# shield.net
KiCad netlist of a schematic drawn in Altium Designer
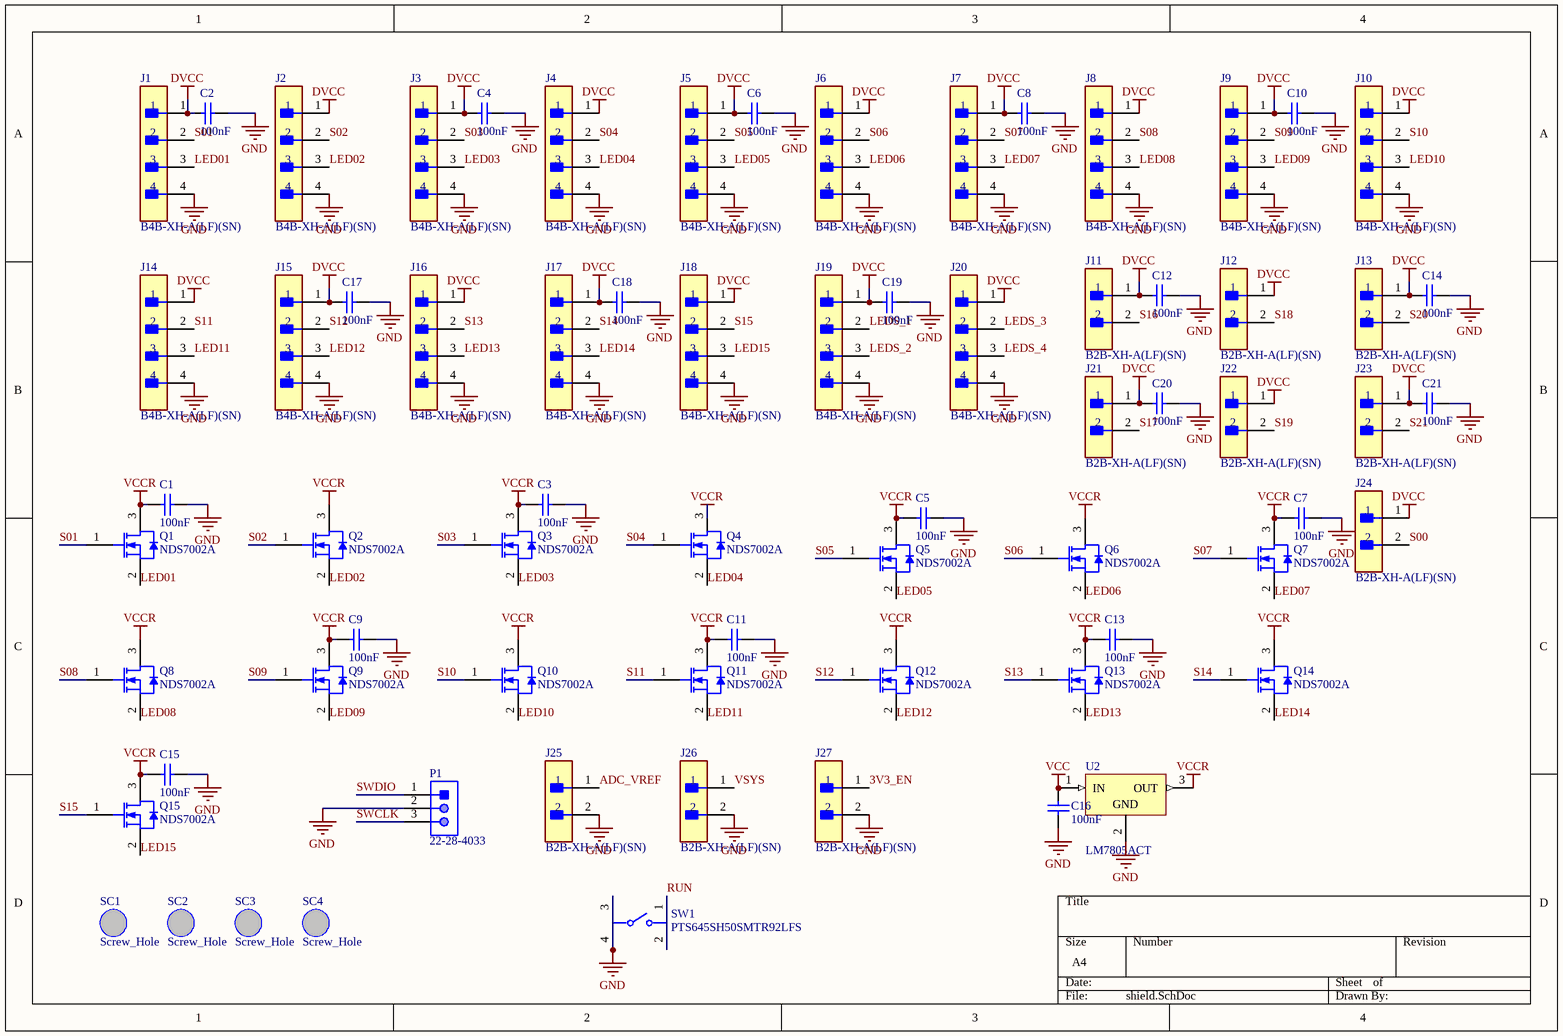
[diagram p0: shield.SchDoc]

(export (version "E")
  (design (tool "Eeschema 10.0.6"))
  (components
    (comp (ref "C1")
      (value "100nF")
      (footprint "0805C")
      (description "Capacitor")
      (fields (field (name "REVIEWED BY") "RM - 2018/08/05"))
      (libsource (lib "DSO") (part "C"))
    )
    (comp (ref "C2")
      (value "100nF")
      (footprint "0805C")
      (description "Capacitor")
      (fields (field (name "REVIEWED BY") "RM - 2018/08/05"))
      (libsource (lib "DSO") (part "C"))
    )
    (comp (ref "C3")
      (value "100nF")
      (footprint "0805C")
      (description "Capacitor")
      (fields (field (name "REVIEWED BY") "RM - 2018/08/05"))
      (libsource (lib "DSO") (part "C"))
    )
    (comp (ref "C4")
      (value "100nF")
      (footprint "0805C")
      (description "Capacitor")
      (fields (field (name "REVIEWED BY") "RM - 2018/08/05"))
      (libsource (lib "DSO") (part "C"))
    )
    (comp (ref "C5")
      (value "100nF")
      (footprint "0805C")
      (description "Capacitor")
      (fields (field (name "REVIEWED BY") "RM - 2018/08/05"))
      (libsource (lib "DSO") (part "C"))
    )
    (comp (ref "C6")
      (value "100nF")
      (footprint "0805C")
      (description "Capacitor")
      (fields (field (name "REVIEWED BY") "RM - 2018/08/05"))
      (libsource (lib "DSO") (part "C"))
    )
    (comp (ref "C7")
      (value "100nF")
      (footprint "0805C")
      (description "Capacitor")
      (fields (field (name "REVIEWED BY") "RM - 2018/08/05"))
      (libsource (lib "DSO") (part "C"))
    )
    (comp (ref "C8")
      (value "100nF")
      (footprint "0805C")
      (description "Capacitor")
      (fields (field (name "REVIEWED BY") "RM - 2018/08/05"))
      (libsource (lib "DSO") (part "C"))
    )
    (comp (ref "C9")
      (value "100nF")
      (footprint "0805C")
      (description "Capacitor")
      (fields (field (name "REVIEWED BY") "RM - 2018/08/05"))
      (libsource (lib "DSO") (part "C"))
    )
    (comp (ref "C10")
      (value "100nF")
      (footprint "0805C")
      (description "Capacitor")
      (fields (field (name "REVIEWED BY") "RM - 2018/08/05"))
      (libsource (lib "DSO") (part "C"))
    )
    (comp (ref "C11")
      (value "100nF")
      (footprint "0805C")
      (description "Capacitor")
      (fields (field (name "REVIEWED BY") "RM - 2018/08/05"))
      (libsource (lib "DSO") (part "C"))
    )
    (comp (ref "C12")
      (value "100nF")
      (footprint "0805C")
      (description "Capacitor")
      (fields (field (name "REVIEWED BY") "RM - 2018/08/05"))
      (libsource (lib "DSO") (part "C"))
    )
    (comp (ref "C13")
      (value "100nF")
      (footprint "0805C")
      (description "Capacitor")
      (fields (field (name "REVIEWED BY") "RM - 2018/08/05"))
      (libsource (lib "DSO") (part "C"))
    )
    (comp (ref "C14")
      (value "100nF")
      (footprint "0805C")
      (description "Capacitor")
      (fields (field (name "REVIEWED BY") "RM - 2018/08/05"))
      (libsource (lib "DSO") (part "C"))
    )
    (comp (ref "C15")
      (value "100nF")
      (footprint "0805C")
      (description "Capacitor")
      (fields (field (name "REVIEWED BY") "RM - 2018/08/05"))
      (libsource (lib "DSO") (part "C"))
    )
    (comp (ref "C16")
      (value "100nF")
      (footprint "0805C")
      (description "Capacitor")
      (fields (field (name "REVIEWED BY") "RM - 2018/08/05"))
      (libsource (lib "DSO") (part "C"))
    )
    (comp (ref "C17")
      (value "100nF")
      (footprint "0805C")
      (description "Capacitor")
      (fields (field (name "REVIEWED BY") "RM - 2018/08/05"))
      (libsource (lib "DSO") (part "C"))
    )
    (comp (ref "C18")
      (value "100nF")
      (footprint "0805C")
      (description "Capacitor")
      (fields (field (name "REVIEWED BY") "RM - 2018/08/05"))
      (libsource (lib "DSO") (part "C"))
    )
    (comp (ref "C19")
      (value "100nF")
      (footprint "0805C")
      (description "Capacitor")
      (fields (field (name "REVIEWED BY") "RM - 2018/08/05"))
      (libsource (lib "DSO") (part "C"))
    )
    (comp (ref "C20")
      (value "100nF")
      (footprint "0805C")
      (description "Capacitor")
      (fields (field (name "REVIEWED BY") "RM - 2018/08/05"))
      (libsource (lib "DSO") (part "C"))
    )
    (comp (ref "C21")
      (value "100nF")
      (footprint "0805C")
      (description "Capacitor")
      (fields (field (name "REVIEWED BY") "RM - 2018/08/05"))
      (libsource (lib "DSO") (part "C"))
    )
    (comp (ref "J1")
      (value "B4B-XH-A(LF)(SN)")
      (footprint "FP-B4B-XH-A_LF_SN-MFG")
      (description "CONN HEADER VERT 4POS 2.5MM")
      (libsource (lib "Altium Content Vault") (part "299a8cea1bdcbc3624fe62c390fa72c"))
    )
    (comp (ref "J2")
      (value "B4B-XH-A(LF)(SN)")
      (footprint "FP-B4B-XH-A_LF_SN-MFG")
      (description "CONN HEADER VERT 4POS 2.5MM")
      (libsource (lib "Altium Content Vault") (part "299a8cea1bdcbc3624fe62c390fa72c"))
    )
    (comp (ref "J3")
      (value "B4B-XH-A(LF)(SN)")
      (footprint "FP-B4B-XH-A_LF_SN-MFG")
      (description "CONN HEADER VERT 4POS 2.5MM")
      (libsource (lib "Altium Content Vault") (part "299a8cea1bdcbc3624fe62c390fa72c"))
    )
    (comp (ref "J4")
      (value "B4B-XH-A(LF)(SN)")
      (footprint "FP-B4B-XH-A_LF_SN-MFG")
      (description "CONN HEADER VERT 4POS 2.5MM")
      (libsource (lib "Altium Content Vault") (part "299a8cea1bdcbc3624fe62c390fa72c"))
    )
    (comp (ref "J5")
      (value "B4B-XH-A(LF)(SN)")
      (footprint "FP-B4B-XH-A_LF_SN-MFG")
      (description "CONN HEADER VERT 4POS 2.5MM")
      (libsource (lib "Altium Content Vault") (part "299a8cea1bdcbc3624fe62c390fa72c"))
    )
    (comp (ref "J6")
      (value "B4B-XH-A(LF)(SN)")
      (footprint "FP-B4B-XH-A_LF_SN-MFG")
      (description "CONN HEADER VERT 4POS 2.5MM")
      (libsource (lib "Altium Content Vault") (part "299a8cea1bdcbc3624fe62c390fa72c"))
    )
    (comp (ref "J7")
      (value "B4B-XH-A(LF)(SN)")
      (footprint "FP-B4B-XH-A_LF_SN-MFG")
      (description "CONN HEADER VERT 4POS 2.5MM")
      (libsource (lib "Altium Content Vault") (part "299a8cea1bdcbc3624fe62c390fa72c"))
    )
    (comp (ref "J8")
      (value "B4B-XH-A(LF)(SN)")
      (footprint "FP-B4B-XH-A_LF_SN-MFG")
      (description "CONN HEADER VERT 4POS 2.5MM")
      (libsource (lib "Altium Content Vault") (part "299a8cea1bdcbc3624fe62c390fa72c"))
    )
    (comp (ref "J9")
      (value "B4B-XH-A(LF)(SN)")
      (footprint "FP-B4B-XH-A_LF_SN-MFG")
      (description "CONN HEADER VERT 4POS 2.5MM")
      (libsource (lib "Altium Content Vault") (part "299a8cea1bdcbc3624fe62c390fa72c"))
    )
    (comp (ref "J10")
      (value "B4B-XH-A(LF)(SN)")
      (footprint "FP-B4B-XH-A_LF_SN-MFG")
      (description "CONN HEADER VERT 4POS 2.5MM")
      (libsource (lib "Altium Content Vault") (part "299a8cea1bdcbc3624fe62c390fa72c"))
    )
    (comp (ref "J11")
      (value "B2B-XH-A(LF)(SN)")
      (footprint "FP-B2B-XH-A_LF_SN-MFG")
      (description "CONN HEADER VERT 2POS 2.5MM")
      (libsource (lib "Altium Content Vault") (part "3bc925449376181038e59eaffc5286c"))
    )
    (comp (ref "J12")
      (value "B2B-XH-A(LF)(SN)")
      (footprint "FP-B2B-XH-A_LF_SN-MFG")
      (description "CONN HEADER VERT 2POS 2.5MM")
      (libsource (lib "Altium Content Vault") (part "3bc925449376181038e59eaffc5286c"))
    )
    (comp (ref "J13")
      (value "B2B-XH-A(LF)(SN)")
      (footprint "FP-B2B-XH-A_LF_SN-MFG")
      (description "CONN HEADER VERT 2POS 2.5MM")
      (libsource (lib "Altium Content Vault") (part "3bc925449376181038e59eaffc5286c"))
    )
    (comp (ref "J14")
      (value "B4B-XH-A(LF)(SN)")
      (footprint "FP-B4B-XH-A_LF_SN-MFG")
      (description "CONN HEADER VERT 4POS 2.5MM")
      (libsource (lib "Altium Content Vault") (part "299a8cea1bdcbc3624fe62c390fa72c"))
    )
    (comp (ref "J15")
      (value "B4B-XH-A(LF)(SN)")
      (footprint "FP-B4B-XH-A_LF_SN-MFG")
      (description "CONN HEADER VERT 4POS 2.5MM")
      (libsource (lib "Altium Content Vault") (part "299a8cea1bdcbc3624fe62c390fa72c"))
    )
    (comp (ref "J16")
      (value "B4B-XH-A(LF)(SN)")
      (footprint "FP-B4B-XH-A_LF_SN-MFG")
      (description "CONN HEADER VERT 4POS 2.5MM")
      (libsource (lib "Altium Content Vault") (part "299a8cea1bdcbc3624fe62c390fa72c"))
    )
    (comp (ref "J17")
      (value "B4B-XH-A(LF)(SN)")
      (footprint "FP-B4B-XH-A_LF_SN-MFG")
      (description "CONN HEADER VERT 4POS 2.5MM")
      (libsource (lib "Altium Content Vault") (part "299a8cea1bdcbc3624fe62c390fa72c"))
    )
    (comp (ref "J18")
      (value "B4B-XH-A(LF)(SN)")
      (footprint "FP-B4B-XH-A_LF_SN-MFG")
      (description "CONN HEADER VERT 4POS 2.5MM")
      (libsource (lib "Altium Content Vault") (part "299a8cea1bdcbc3624fe62c390fa72c"))
    )
    (comp (ref "J19")
      (value "B4B-XH-A(LF)(SN)")
      (footprint "FP-B4B-XH-A_LF_SN-MFG")
      (description "CONN HEADER VERT 4POS 2.5MM")
      (libsource (lib "Altium Content Vault") (part "299a8cea1bdcbc3624fe62c390fa72c"))
    )
    (comp (ref "J20")
      (value "B4B-XH-A(LF)(SN)")
      (footprint "FP-B4B-XH-A_LF_SN-MFG")
      (description "CONN HEADER VERT 4POS 2.5MM")
      (libsource (lib "Altium Content Vault") (part "299a8cea1bdcbc3624fe62c390fa72c"))
    )
    (comp (ref "J21")
      (value "B2B-XH-A(LF)(SN)")
      (footprint "FP-B2B-XH-A_LF_SN-MFG")
      (description "CONN HEADER VERT 2POS 2.5MM")
      (libsource (lib "Altium Content Vault") (part "3bc925449376181038e59eaffc5286c"))
    )
    (comp (ref "J22")
      (value "B2B-XH-A(LF)(SN)")
      (footprint "FP-B2B-XH-A_LF_SN-MFG")
      (description "CONN HEADER VERT 2POS 2.5MM")
      (libsource (lib "Altium Content Vault") (part "3bc925449376181038e59eaffc5286c"))
    )
    (comp (ref "J23")
      (value "B2B-XH-A(LF)(SN)")
      (footprint "FP-B2B-XH-A_LF_SN-MFG")
      (description "CONN HEADER VERT 2POS 2.5MM")
      (libsource (lib "Altium Content Vault") (part "3bc925449376181038e59eaffc5286c"))
    )
    (comp (ref "J24")
      (value "B2B-XH-A(LF)(SN)")
      (footprint "FP-B2B-XH-A_LF_SN-MFG")
      (description "CONN HEADER VERT 2POS 2.5MM")
      (libsource (lib "Altium Content Vault") (part "3bc925449376181038e59eaffc5286c"))
    )
    (comp (ref "J25")
      (value "B2B-XH-A(LF)(SN)")
      (footprint "FP-B2B-XH-A_LF_SN-MFG")
      (description "CONN HEADER VERT 2POS 2.5MM")
      (libsource (lib "Altium Content Vault") (part "3bc925449376181038e59eaffc5286c"))
    )
    (comp (ref "J26")
      (value "B2B-XH-A(LF)(SN)")
      (footprint "FP-B2B-XH-A_LF_SN-MFG")
      (description "CONN HEADER VERT 2POS 2.5MM")
      (libsource (lib "Altium Content Vault") (part "3bc925449376181038e59eaffc5286c"))
    )
    (comp (ref "J27")
      (value "B2B-XH-A(LF)(SN)")
      (footprint "FP-B2B-XH-A_LF_SN-MFG")
      (description "CONN HEADER VERT 2POS 2.5MM")
      (libsource (lib "Altium Content Vault") (part "3bc925449376181038e59eaffc5286c"))
    )
    (comp (ref "P1")
      (value "22-28-4033")
      (footprint "MOLX-22-28-4033_V")
      (description "Male Header, Pitch 2.54 mm, 1 x 3 Position, Height 8.38 mm, Tail Length 3.18 mm, RoHS, Bulk")
      (fields (field (name "MANUFACTURER") "Molex"))
      (libsource (lib "Altium Content Vault") (part "CN-1P-M-R3"))
    )
    (comp (ref "Q1")
      (value "NDS7002A")
      (footprint "FAIR-SOT23-3_V")
      (fields (field (name "MANUFACTURER") "Fairchild Semiconductor"))
      (libsource (lib "Altium Content Vault") (part "NEMOS-GSD-3"))
    )
    (comp (ref "Q2")
      (value "NDS7002A")
      (footprint "FAIR-SOT23-3_V")
      (fields (field (name "MANUFACTURER") "Fairchild Semiconductor"))
      (libsource (lib "Altium Content Vault") (part "NEMOS-GSD-3"))
    )
    (comp (ref "Q3")
      (value "NDS7002A")
      (footprint "FAIR-SOT23-3_V")
      (fields (field (name "MANUFACTURER") "Fairchild Semiconductor"))
      (libsource (lib "Altium Content Vault") (part "NEMOS-GSD-3"))
    )
    (comp (ref "Q4")
      (value "NDS7002A")
      (footprint "FAIR-SOT23-3_V")
      (fields (field (name "MANUFACTURER") "Fairchild Semiconductor"))
      (libsource (lib "Altium Content Vault") (part "NEMOS-GSD-3"))
    )
    (comp (ref "Q5")
      (value "NDS7002A")
      (footprint "FAIR-SOT23-3_V")
      (fields (field (name "MANUFACTURER") "Fairchild Semiconductor"))
      (libsource (lib "Altium Content Vault") (part "NEMOS-GSD-3"))
    )
    (comp (ref "Q6")
      (value "NDS7002A")
      (footprint "FAIR-SOT23-3_V")
      (fields (field (name "MANUFACTURER") "Fairchild Semiconductor"))
      (libsource (lib "Altium Content Vault") (part "NEMOS-GSD-3"))
    )
    (comp (ref "Q7")
      (value "NDS7002A")
      (footprint "FAIR-SOT23-3_V")
      (fields (field (name "MANUFACTURER") "Fairchild Semiconductor"))
      (libsource (lib "Altium Content Vault") (part "NEMOS-GSD-3"))
    )
    (comp (ref "Q8")
      (value "NDS7002A")
      (footprint "FAIR-SOT23-3_V")
      (fields (field (name "MANUFACTURER") "Fairchild Semiconductor"))
      (libsource (lib "Altium Content Vault") (part "NEMOS-GSD-3"))
    )
    (comp (ref "Q9")
      (value "NDS7002A")
      (footprint "FAIR-SOT23-3_V")
      (fields (field (name "MANUFACTURER") "Fairchild Semiconductor"))
      (libsource (lib "Altium Content Vault") (part "NEMOS-GSD-3"))
    )
    (comp (ref "Q10")
      (value "NDS7002A")
      (footprint "FAIR-SOT23-3_V")
      (fields (field (name "MANUFACTURER") "Fairchild Semiconductor"))
      (libsource (lib "Altium Content Vault") (part "NEMOS-GSD-3"))
    )
    (comp (ref "Q11")
      (value "NDS7002A")
      (footprint "FAIR-SOT23-3_V")
      (fields (field (name "MANUFACTURER") "Fairchild Semiconductor"))
      (libsource (lib "Altium Content Vault") (part "NEMOS-GSD-3"))
    )
    (comp (ref "Q12")
      (value "NDS7002A")
      (footprint "FAIR-SOT23-3_V")
      (fields (field (name "MANUFACTURER") "Fairchild Semiconductor"))
      (libsource (lib "Altium Content Vault") (part "NEMOS-GSD-3"))
    )
    (comp (ref "Q13")
      (value "NDS7002A")
      (footprint "FAIR-SOT23-3_V")
      (fields (field (name "MANUFACTURER") "Fairchild Semiconductor"))
      (libsource (lib "Altium Content Vault") (part "NEMOS-GSD-3"))
    )
    (comp (ref "Q14")
      (value "NDS7002A")
      (footprint "FAIR-SOT23-3_V")
      (fields (field (name "MANUFACTURER") "Fairchild Semiconductor"))
      (libsource (lib "Altium Content Vault") (part "NEMOS-GSD-3"))
    )
    (comp (ref "Q15")
      (value "NDS7002A")
      (footprint "FAIR-SOT23-3_V")
      (fields (field (name "MANUFACTURER") "Fairchild Semiconductor"))
      (libsource (lib "Altium Content Vault") (part "NEMOS-GSD-3"))
    )
    (comp (ref "SC1")
      (value "Screw_Hole")
      (footprint "Screw_Hole")
      (description "Screw Hole")
      (libsource (lib "DSO") (part "Screw_Hole"))
    )
    (comp (ref "SC2")
      (value "Screw_Hole")
      (footprint "Screw_Hole")
      (description "Screw Hole")
      (libsource (lib "DSO") (part "Screw_Hole"))
    )
    (comp (ref "SC3")
      (value "Screw_Hole")
      (footprint "Screw_Hole")
      (description "Screw Hole")
      (libsource (lib "DSO") (part "Screw_Hole"))
    )
    (comp (ref "SC4")
      (value "Screw_Hole")
      (footprint "Screw_Hole")
      (description "Screw Hole")
      (libsource (lib "DSO") (part "Screw_Hole"))
    )
    (comp (ref "SW1")
      (value "PTS645SH50SMTR92LFS")
      (footprint "FP-PTS645SH50SMTR92LFS-MFG")
      (description "SWITCH TACTILE SPST-NO 0.05A 12V")
      (libsource (lib "Altium Content Vault") (part "1adf0dd01260c80cf25a44bfd6b99ba"))
    )
    (comp (ref "U2")
      (value "LM7805ACT")
      (footprint "FAIR-TO-220-3")
      (description "Positive Voltage Regulator, 5 V, 1 A, 0 to 125 degC, 3-Pin TO-220, RoHS, Tube")
      (fields (field (name "MANUFACTURER") "Fairchild"))
      (libsource (lib "Altium Content Vault") (part "FAIR-LM7805CT-TO220-3"))
    )
  )
  (nets
    (net (code "1") (name "/3V3_EN") (class "Default")
      (node (ref "J27") (pin "1") (pinfunction "1_1") (pintype "passive"))
    )
    (net (code "2") (name "/ADC_VREF") (class "Default")
      (node (ref "J25") (pin "1") (pinfunction "1_1") (pintype "passive"))
    )
    (net (code "3") (name "/LED01") (class "Default")
      (node (ref "J1") (pin "3") (pinfunction "3_3") (pintype "passive"))
      (node (ref "Q1") (pin "2") (pinfunction "S_2") (pintype "passive"))
    )
    (net (code "4") (name "/LED02") (class "Default")
      (node (ref "J2") (pin "3") (pinfunction "3_3") (pintype "passive"))
      (node (ref "Q2") (pin "2") (pinfunction "S_2") (pintype "passive"))
    )
    (net (code "5") (name "/LED03") (class "Default")
      (node (ref "J3") (pin "3") (pinfunction "3_3") (pintype "passive"))
      (node (ref "Q3") (pin "2") (pinfunction "S_2") (pintype "passive"))
    )
    (net (code "6") (name "/LED04") (class "Default")
      (node (ref "J4") (pin "3") (pinfunction "3_3") (pintype "passive"))
      (node (ref "Q4") (pin "2") (pinfunction "S_2") (pintype "passive"))
    )
    (net (code "7") (name "/LED05") (class "Default")
      (node (ref "J5") (pin "3") (pinfunction "3_3") (pintype "passive"))
      (node (ref "Q5") (pin "2") (pinfunction "S_2") (pintype "passive"))
    )
    (net (code "8") (name "/LED06") (class "Default")
      (node (ref "J6") (pin "3") (pinfunction "3_3") (pintype "passive"))
      (node (ref "Q6") (pin "2") (pinfunction "S_2") (pintype "passive"))
    )
    (net (code "9") (name "/LED07") (class "Default")
      (node (ref "J7") (pin "3") (pinfunction "3_3") (pintype "passive"))
      (node (ref "Q7") (pin "2") (pinfunction "S_2") (pintype "passive"))
    )
    (net (code "10") (name "/LED08") (class "Default")
      (node (ref "J8") (pin "3") (pinfunction "3_3") (pintype "passive"))
      (node (ref "Q8") (pin "2") (pinfunction "S_2") (pintype "passive"))
    )
    (net (code "11") (name "/LED09") (class "Default")
      (node (ref "J9") (pin "3") (pinfunction "3_3") (pintype "passive"))
      (node (ref "Q9") (pin "2") (pinfunction "S_2") (pintype "passive"))
    )
    (net (code "12") (name "/LED10") (class "Default")
      (node (ref "J10") (pin "3") (pinfunction "3_3") (pintype "passive"))
      (node (ref "Q10") (pin "2") (pinfunction "S_2") (pintype "passive"))
    )
    (net (code "13") (name "/LED11") (class "Default")
      (node (ref "J14") (pin "3") (pinfunction "3_3") (pintype "passive"))
      (node (ref "Q11") (pin "2") (pinfunction "S_2") (pintype "passive"))
    )
    (net (code "14") (name "/LED12") (class "Default")
      (node (ref "J15") (pin "3") (pinfunction "3_3") (pintype "passive"))
      (node (ref "Q12") (pin "2") (pinfunction "S_2") (pintype "passive"))
    )
    (net (code "15") (name "/LED13") (class "Default")
      (node (ref "J16") (pin "3") (pinfunction "3_3") (pintype "passive"))
      (node (ref "Q13") (pin "2") (pinfunction "S_2") (pintype "passive"))
    )
    (net (code "16") (name "/LED14") (class "Default")
      (node (ref "J17") (pin "3") (pinfunction "3_3") (pintype "passive"))
      (node (ref "Q14") (pin "2") (pinfunction "S_2") (pintype "passive"))
    )
    (net (code "17") (name "/LED15") (class "Default")
      (node (ref "J18") (pin "3") (pinfunction "3_3") (pintype "passive"))
      (node (ref "Q15") (pin "2") (pinfunction "S_2") (pintype "passive"))
    )
    (net (code "18") (name "/LEDS_1") (class "Default")
      (node (ref "J19") (pin "2") (pinfunction "2_2") (pintype "passive"))
    )
    (net (code "19") (name "/LEDS_2") (class "Default")
      (node (ref "J19") (pin "3") (pinfunction "3_3") (pintype "passive"))
    )
    (net (code "20") (name "/LEDS_3") (class "Default")
      (node (ref "J20") (pin "2") (pinfunction "2_2") (pintype "passive"))
    )
    (net (code "21") (name "/LEDS_4") (class "Default")
      (node (ref "J20") (pin "3") (pinfunction "3_3") (pintype "passive"))
    )
    (net (code "22") (name "/RUN") (class "Default")
      (node (ref "SW1") (pin "1") (pinfunction "1_1") (pintype "passive"))
      (node (ref "SW1") (pin "2") (pinfunction "2_2") (pintype "passive"))
    )
    (net (code "23") (name "/S00") (class "Default")
      (node (ref "J24") (pin "2") (pinfunction "2_2") (pintype "passive"))
    )
    (net (code "24") (name "/S01") (class "Default")
      (node (ref "J1") (pin "2") (pinfunction "2_2") (pintype "passive"))
      (node (ref "Q1") (pin "1") (pinfunction "G_1") (pintype "passive"))
    )
    (net (code "25") (name "/S02") (class "Default")
      (node (ref "J2") (pin "2") (pinfunction "2_2") (pintype "passive"))
      (node (ref "Q2") (pin "1") (pinfunction "G_1") (pintype "passive"))
    )
    (net (code "26") (name "/S03") (class "Default")
      (node (ref "J3") (pin "2") (pinfunction "2_2") (pintype "passive"))
      (node (ref "Q3") (pin "1") (pinfunction "G_1") (pintype "passive"))
    )
    (net (code "27") (name "/S04") (class "Default")
      (node (ref "J4") (pin "2") (pinfunction "2_2") (pintype "passive"))
      (node (ref "Q4") (pin "1") (pinfunction "G_1") (pintype "passive"))
    )
    (net (code "28") (name "/S05") (class "Default")
      (node (ref "J5") (pin "2") (pinfunction "2_2") (pintype "passive"))
      (node (ref "Q5") (pin "1") (pinfunction "G_1") (pintype "passive"))
    )
    (net (code "29") (name "/S06") (class "Default")
      (node (ref "J6") (pin "2") (pinfunction "2_2") (pintype "passive"))
      (node (ref "Q6") (pin "1") (pinfunction "G_1") (pintype "passive"))
    )
    (net (code "30") (name "/S07") (class "Default")
      (node (ref "J7") (pin "2") (pinfunction "2_2") (pintype "passive"))
      (node (ref "Q7") (pin "1") (pinfunction "G_1") (pintype "passive"))
    )
    (net (code "31") (name "/S08") (class "Default")
      (node (ref "J8") (pin "2") (pinfunction "2_2") (pintype "passive"))
      (node (ref "Q8") (pin "1") (pinfunction "G_1") (pintype "passive"))
    )
    (net (code "32") (name "/S09") (class "Default")
      (node (ref "J9") (pin "2") (pinfunction "2_2") (pintype "passive"))
      (node (ref "Q9") (pin "1") (pinfunction "G_1") (pintype "passive"))
    )
    (net (code "33") (name "/S10") (class "Default")
      (node (ref "J10") (pin "2") (pinfunction "2_2") (pintype "passive"))
      (node (ref "Q10") (pin "1") (pinfunction "G_1") (pintype "passive"))
    )
    (net (code "34") (name "/S11") (class "Default")
      (node (ref "J14") (pin "2") (pinfunction "2_2") (pintype "passive"))
      (node (ref "Q11") (pin "1") (pinfunction "G_1") (pintype "passive"))
    )
    (net (code "35") (name "/S12") (class "Default")
      (node (ref "J15") (pin "2") (pinfunction "2_2") (pintype "passive"))
      (node (ref "Q12") (pin "1") (pinfunction "G_1") (pintype "passive"))
    )
    (net (code "36") (name "/S13") (class "Default")
      (node (ref "J16") (pin "2") (pinfunction "2_2") (pintype "passive"))
      (node (ref "Q13") (pin "1") (pinfunction "G_1") (pintype "passive"))
    )
    (net (code "37") (name "/S14") (class "Default")
      (node (ref "J17") (pin "2") (pinfunction "2_2") (pintype "passive"))
      (node (ref "Q14") (pin "1") (pinfunction "G_1") (pintype "passive"))
    )
    (net (code "38") (name "/S15") (class "Default")
      (node (ref "J18") (pin "2") (pinfunction "2_2") (pintype "passive"))
      (node (ref "Q15") (pin "1") (pinfunction "G_1") (pintype "passive"))
    )
    (net (code "39") (name "/S16") (class "Default")
      (node (ref "J11") (pin "2") (pinfunction "2_2") (pintype "passive"))
    )
    (net (code "40") (name "/S17") (class "Default")
      (node (ref "J21") (pin "2") (pinfunction "2_2") (pintype "passive"))
    )
    (net (code "41") (name "/S18") (class "Default")
      (node (ref "J12") (pin "2") (pinfunction "2_2") (pintype "passive"))
    )
    (net (code "42") (name "/S19") (class "Default")
      (node (ref "J22") (pin "2") (pinfunction "2_2") (pintype "passive"))
    )
    (net (code "43") (name "/S20") (class "Default")
      (node (ref "J13") (pin "2") (pinfunction "2_2") (pintype "passive"))
    )
    (net (code "44") (name "/S21") (class "Default")
      (node (ref "J23") (pin "2") (pinfunction "2_2") (pintype "passive"))
    )
    (net (code "45") (name "/SWCLK") (class "Default")
      (node (ref "P1") (pin "3") (pinfunction "3_3") (pintype "passive"))
    )
    (net (code "46") (name "/SWDIO") (class "Default")
      (node (ref "P1") (pin "1") (pinfunction "1_1") (pintype "passive"))
    )
    (net (code "47") (name "/VSYS") (class "Default")
      (node (ref "J26") (pin "1") (pinfunction "1_1") (pintype "passive"))
    )
    (net (code "48") (name "DVCC") (class "Default")
      (node (ref "C10") (pin "1") (pinfunction "1_1") (pintype "passive"))
      (node (ref "C12") (pin "1") (pinfunction "1_1") (pintype "passive"))
      (node (ref "C14") (pin "1") (pinfunction "1_1") (pintype "passive"))
      (node (ref "C17") (pin "1") (pinfunction "1_1") (pintype "passive"))
      (node (ref "C18") (pin "1") (pinfunction "1_1") (pintype "passive"))
      (node (ref "C19") (pin "1") (pinfunction "1_1") (pintype "passive"))
      (node (ref "C2") (pin "1") (pinfunction "1_1") (pintype "passive"))
      (node (ref "C20") (pin "1") (pinfunction "1_1") (pintype "passive"))
      (node (ref "C21") (pin "1") (pinfunction "1_1") (pintype "passive"))
      (node (ref "C4") (pin "1") (pinfunction "1_1") (pintype "passive"))
      (node (ref "C6") (pin "1") (pinfunction "1_1") (pintype "passive"))
      (node (ref "C8") (pin "1") (pinfunction "1_1") (pintype "passive"))
      (node (ref "J1") (pin "1") (pinfunction "1_1") (pintype "passive"))
      (node (ref "J10") (pin "1") (pinfunction "1_1") (pintype "passive"))
      (node (ref "J11") (pin "1") (pinfunction "1_1") (pintype "passive"))
      (node (ref "J12") (pin "1") (pinfunction "1_1") (pintype "passive"))
      (node (ref "J13") (pin "1") (pinfunction "1_1") (pintype "passive"))
      (node (ref "J14") (pin "1") (pinfunction "1_1") (pintype "passive"))
      (node (ref "J15") (pin "1") (pinfunction "1_1") (pintype "passive"))
      (node (ref "J16") (pin "1") (pinfunction "1_1") (pintype "passive"))
      (node (ref "J17") (pin "1") (pinfunction "1_1") (pintype "passive"))
      (node (ref "J18") (pin "1") (pinfunction "1_1") (pintype "passive"))
      (node (ref "J19") (pin "1") (pinfunction "1_1") (pintype "passive"))
      (node (ref "J2") (pin "1") (pinfunction "1_1") (pintype "passive"))
      (node (ref "J20") (pin "1") (pinfunction "1_1") (pintype "passive"))
      (node (ref "J21") (pin "1") (pinfunction "1_1") (pintype "passive"))
      (node (ref "J22") (pin "1") (pinfunction "1_1") (pintype "passive"))
      (node (ref "J23") (pin "1") (pinfunction "1_1") (pintype "passive"))
      (node (ref "J24") (pin "1") (pinfunction "1_1") (pintype "passive"))
      (node (ref "J3") (pin "1") (pinfunction "1_1") (pintype "passive"))
      (node (ref "J4") (pin "1") (pinfunction "1_1") (pintype "passive"))
      (node (ref "J5") (pin "1") (pinfunction "1_1") (pintype "passive"))
      (node (ref "J6") (pin "1") (pinfunction "1_1") (pintype "passive"))
      (node (ref "J7") (pin "1") (pinfunction "1_1") (pintype "passive"))
      (node (ref "J8") (pin "1") (pinfunction "1_1") (pintype "passive"))
      (node (ref "J9") (pin "1") (pinfunction "1_1") (pintype "passive"))
    )
    (net (code "49") (name "GND") (class "Default")
      (node (ref "C1") (pin "2") (pinfunction "2_2") (pintype "passive"))
      (node (ref "C10") (pin "2") (pinfunction "2_2") (pintype "passive"))
      (node (ref "C11") (pin "2") (pinfunction "2_2") (pintype "passive"))
      (node (ref "C12") (pin "2") (pinfunction "2_2") (pintype "passive"))
      (node (ref "C13") (pin "2") (pinfunction "2_2") (pintype "passive"))
      (node (ref "C14") (pin "2") (pinfunction "2_2") (pintype "passive"))
      (node (ref "C15") (pin "2") (pinfunction "2_2") (pintype "passive"))
      (node (ref "C16") (pin "1") (pinfunction "1_1") (pintype "passive"))
      (node (ref "C17") (pin "2") (pinfunction "2_2") (pintype "passive"))
      (node (ref "C18") (pin "2") (pinfunction "2_2") (pintype "passive"))
      (node (ref "C19") (pin "2") (pinfunction "2_2") (pintype "passive"))
      (node (ref "C2") (pin "2") (pinfunction "2_2") (pintype "passive"))
      (node (ref "C20") (pin "2") (pinfunction "2_2") (pintype "passive"))
      (node (ref "C21") (pin "2") (pinfunction "2_2") (pintype "passive"))
      (node (ref "C3") (pin "2") (pinfunction "2_2") (pintype "passive"))
      (node (ref "C4") (pin "2") (pinfunction "2_2") (pintype "passive"))
      (node (ref "C5") (pin "2") (pinfunction "2_2") (pintype "passive"))
      (node (ref "C6") (pin "2") (pinfunction "2_2") (pintype "passive"))
      (node (ref "C7") (pin "2") (pinfunction "2_2") (pintype "passive"))
      (node (ref "C8") (pin "2") (pinfunction "2_2") (pintype "passive"))
      (node (ref "C9") (pin "2") (pinfunction "2_2") (pintype "passive"))
      (node (ref "J1") (pin "4") (pinfunction "4_4") (pintype "passive"))
      (node (ref "J10") (pin "4") (pinfunction "4_4") (pintype "passive"))
      (node (ref "J14") (pin "4") (pinfunction "4_4") (pintype "passive"))
      (node (ref "J15") (pin "4") (pinfunction "4_4") (pintype "passive"))
      (node (ref "J16") (pin "4") (pinfunction "4_4") (pintype "passive"))
      (node (ref "J17") (pin "4") (pinfunction "4_4") (pintype "passive"))
      (node (ref "J18") (pin "4") (pinfunction "4_4") (pintype "passive"))
      (node (ref "J19") (pin "4") (pinfunction "4_4") (pintype "passive"))
      (node (ref "J2") (pin "4") (pinfunction "4_4") (pintype "passive"))
      (node (ref "J20") (pin "4") (pinfunction "4_4") (pintype "passive"))
      (node (ref "J25") (pin "2") (pinfunction "2_2") (pintype "passive"))
      (node (ref "J26") (pin "2") (pinfunction "2_2") (pintype "passive"))
      (node (ref "J27") (pin "2") (pinfunction "2_2") (pintype "passive"))
      (node (ref "J3") (pin "4") (pinfunction "4_4") (pintype "passive"))
      (node (ref "J4") (pin "4") (pinfunction "4_4") (pintype "passive"))
      (node (ref "J5") (pin "4") (pinfunction "4_4") (pintype "passive"))
      (node (ref "J6") (pin "4") (pinfunction "4_4") (pintype "passive"))
      (node (ref "J7") (pin "4") (pinfunction "4_4") (pintype "passive"))
      (node (ref "J8") (pin "4") (pinfunction "4_4") (pintype "passive"))
      (node (ref "J9") (pin "4") (pinfunction "4_4") (pintype "passive"))
      (node (ref "P1") (pin "2") (pinfunction "2_2") (pintype "passive"))
      (node (ref "SW1") (pin "3") (pinfunction "3_3") (pintype "passive"))
      (node (ref "SW1") (pin "4") (pinfunction "4_4") (pintype "passive"))
      (node (ref "U2") (pin "2") (pinfunction "GND_2") (pintype "power_in"))
    )
    (net (code "50") (name "VCC") (class "Default")
      (node (ref "C16") (pin "2") (pinfunction "2_2") (pintype "passive"))
      (node (ref "U2") (pin "1") (pinfunction "IN_1") (pintype "input"))
    )
    (net (code "51") (name "VCCR") (class "Default")
      (node (ref "C1") (pin "1") (pinfunction "1_1") (pintype "passive"))
      (node (ref "C11") (pin "1") (pinfunction "1_1") (pintype "passive"))
      (node (ref "C13") (pin "1") (pinfunction "1_1") (pintype "passive"))
      (node (ref "C15") (pin "1") (pinfunction "1_1") (pintype "passive"))
      (node (ref "C3") (pin "1") (pinfunction "1_1") (pintype "passive"))
      (node (ref "C5") (pin "1") (pinfunction "1_1") (pintype "passive"))
      (node (ref "C7") (pin "1") (pinfunction "1_1") (pintype "passive"))
      (node (ref "C9") (pin "1") (pinfunction "1_1") (pintype "passive"))
      (node (ref "Q1") (pin "3") (pinfunction "D_3") (pintype "passive"))
      (node (ref "Q10") (pin "3") (pinfunction "D_3") (pintype "passive"))
      (node (ref "Q11") (pin "3") (pinfunction "D_3") (pintype "passive"))
      (node (ref "Q12") (pin "3") (pinfunction "D_3") (pintype "passive"))
      (node (ref "Q13") (pin "3") (pinfunction "D_3") (pintype "passive"))
      (node (ref "Q14") (pin "3") (pinfunction "D_3") (pintype "passive"))
      (node (ref "Q15") (pin "3") (pinfunction "D_3") (pintype "passive"))
      (node (ref "Q2") (pin "3") (pinfunction "D_3") (pintype "passive"))
      (node (ref "Q3") (pin "3") (pinfunction "D_3") (pintype "passive"))
      (node (ref "Q4") (pin "3") (pinfunction "D_3") (pintype "passive"))
      (node (ref "Q5") (pin "3") (pinfunction "D_3") (pintype "passive"))
      (node (ref "Q6") (pin "3") (pinfunction "D_3") (pintype "passive"))
      (node (ref "Q7") (pin "3") (pinfunction "D_3") (pintype "passive"))
      (node (ref "Q8") (pin "3") (pinfunction "D_3") (pintype "passive"))
      (node (ref "Q9") (pin "3") (pinfunction "D_3") (pintype "passive"))
      (node (ref "U2") (pin "3") (pinfunction "OUT_3") (pintype "output"))
    )
  )
)
